# ThermoEagle.net
KiCad netlist of a schematic drawn in EAGLE
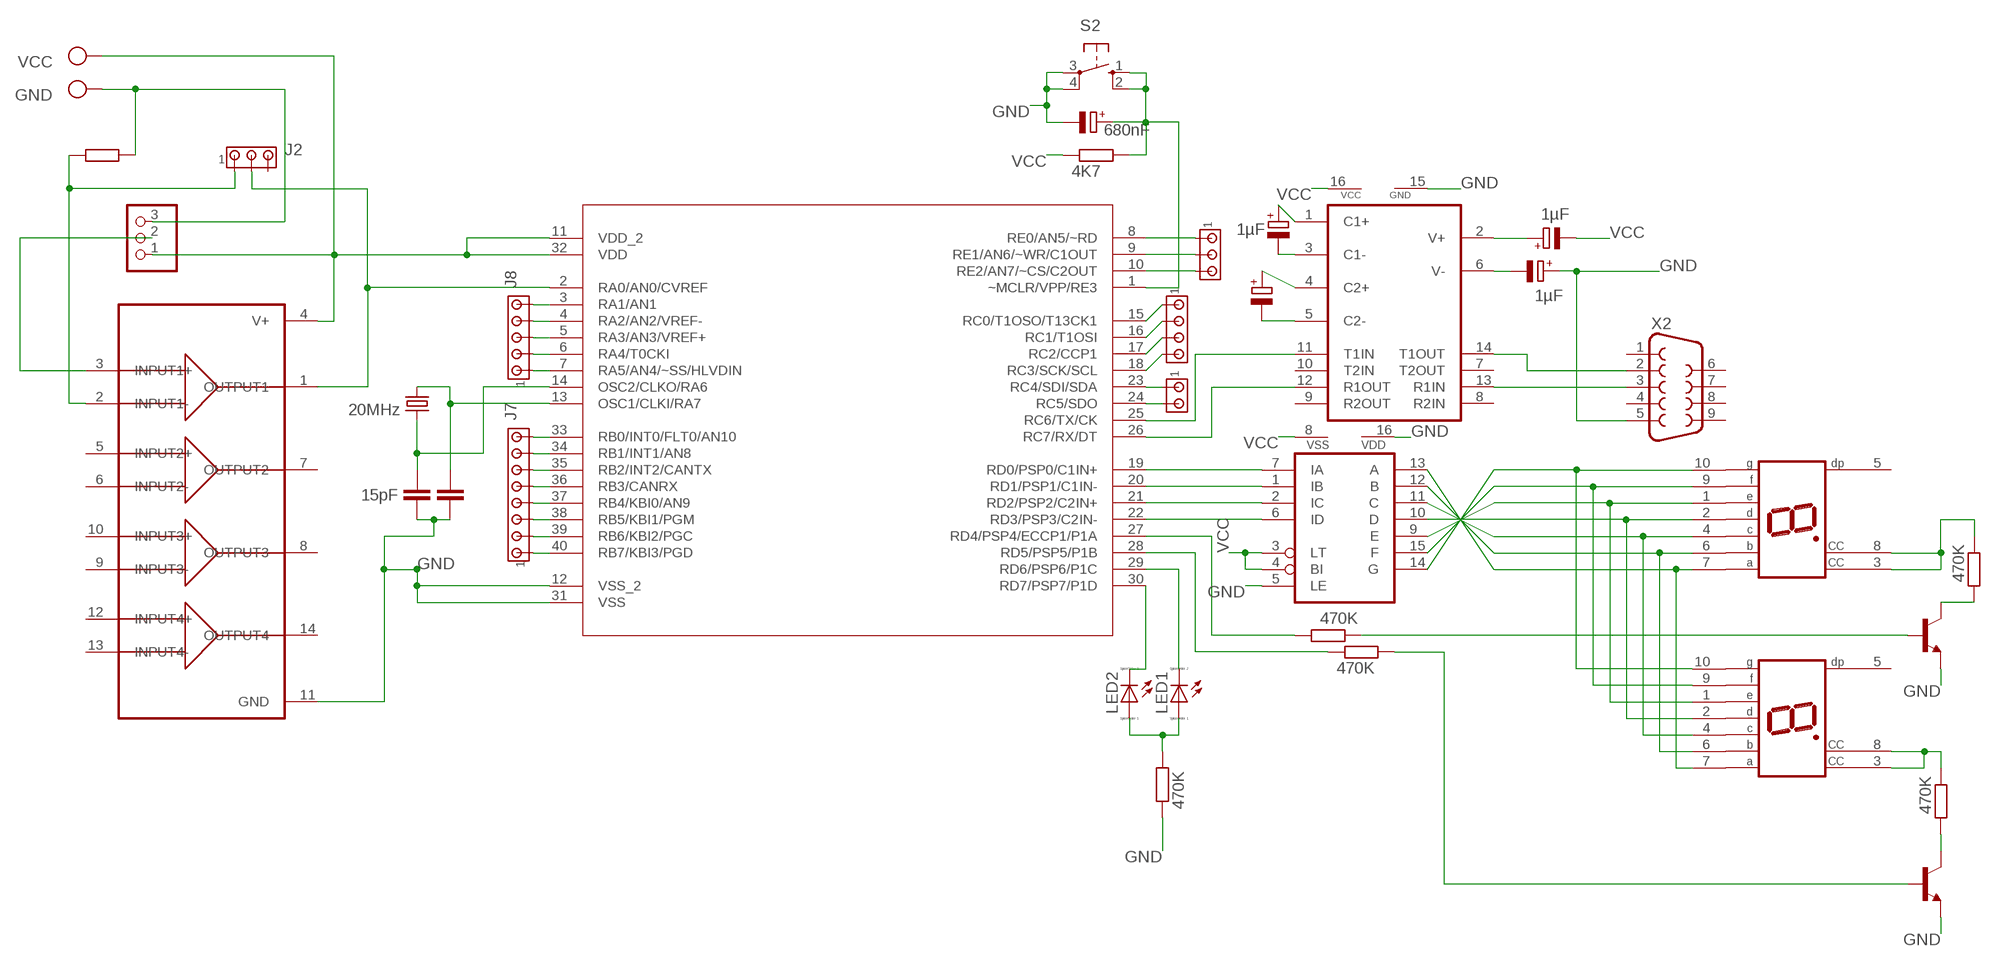
[diagram p0: schematic, sheet 1]

(export (version "E")
  (design (tool "Eeschema 10.0.6"))
  (components
    (comp (ref "C1")
      (value "1µF")
      (footprint "eagle-import:B45181B")
      (libsource (lib "eagle-import") (part "CPOL-EUB45181B"))
    )
    (comp (ref "C2")
      (value "1µF")
      (footprint "eagle-import:B45181B")
      (libsource (lib "eagle-import") (part "CPOL-EUB45181B"))
    )
    (comp (ref "C3")
      (value "1µF")
      (footprint "eagle-import:B45181B")
      (libsource (lib "eagle-import") (part "CPOL-EUB45181B"))
    )
    (comp (ref "C5")
      (value "1µF")
      (footprint "eagle-import:B45181B")
      (libsource (lib "eagle-import") (part "CPOL-EUB45181B"))
    )
    (comp (ref "C6")
      (value "15pF")
      (footprint "eagle-import:C050-025X075")
      (libsource (lib "eagle-import") (part "C-EU050-025X075"))
    )
    (comp (ref "C7")
      (value "C-EU050-025X075")
      (footprint "eagle-import:C050-025X075")
      (libsource (lib "eagle-import") (part "C-EU050-025X075"))
    )
    (comp (ref "C8")
      (value "680nF")
      (footprint "eagle-import:B45181C")
      (libsource (lib "eagle-import") (part "CPOL-EUB45181C"))
    )
    (comp (ref "DIS1")
      (value "HD-H103")
      (footprint "eagle-import:HDSP-M")
      (libsource (lib "eagle-import") (part "HD-H103"))
    )
    (comp (ref "DIS2")
      (value "HD-H103")
      (footprint "eagle-import:HDSP-M")
      (libsource (lib "eagle-import") (part "HD-H103"))
    )
    (comp (ref "IC1")
      (value "MAX232")
      (footprint "eagle-import:DIL16")
      (fields (field (name "MF") "MAXIM") (field (name "MPN") "MAX232ACPE+"))
      (libsource (lib "eagle-import") (part "MAX232"))
    )
    (comp (ref "IC2")
      (value "4511N")
      (footprint "eagle-import:DIL16")
      (libsource (lib "eagle-import") (part "4511N"))
    )
    (comp (ref "J1")
      (value "MTA04-100")
      (footprint "eagle-import:10X04MTA")
      (libsource (lib "eagle-import") (part "MTA04-100"))
    )
    (comp (ref "J2")
      (value "MTA03-100")
      (footprint "eagle-import:10X03MTA")
      (libsource (lib "eagle-import") (part "MTA03-100"))
    )
    (comp (ref "J3")
      (value "MTA02-100")
      (footprint "eagle-import:10X02MTA")
      (libsource (lib "eagle-import") (part "MTA02-100"))
    )
    (comp (ref "J4")
      (value "MTA03-100")
      (footprint "eagle-import:10X03MTA")
      (libsource (lib "eagle-import") (part "MTA03-100"))
    )
    (comp (ref "J7")
      (value "MTA08-100")
      (footprint "eagle-import:10X08MTA")
      (libsource (lib "eagle-import") (part "MTA08-100"))
    )
    (comp (ref "J8")
      (value "MTA05-100")
      (footprint "eagle-import:10X05MTA")
      (libsource (lib "eagle-import") (part "MTA05-100"))
    )
    (comp (ref "JP1")
      (value "PINHD-1X3")
      (footprint "eagle-import:1X03")
      (libsource (lib "eagle-import") (part "PINHD-1X3"))
    )
    (comp (ref "LED1")
      (value "LED_ELD260")
      (footprint "eagle-import:LED_LD260")
      (libsource (lib "eagle-import") (part "LED_ELD260"))
    )
    (comp (ref "LED2")
      (value "LED_ELD260")
      (footprint "eagle-import:LED_LD260")
      (libsource (lib "eagle-import") (part "LED_ELD260"))
    )
    (comp (ref "Q1")
      (value "20MHz")
      (footprint "eagle-import:HC18U-V")
      (libsource (lib "eagle-import") (part "CRYSTALHC18U-V"))
    )
    (comp (ref "R1")
      (value "470K")
      (footprint "eagle-import:0207_7")
      (libsource (lib "eagle-import") (part "R-EU_0207/7"))
    )
    (comp (ref "R2")
      (value "470K")
      (footprint "eagle-import:0207_7")
      (libsource (lib "eagle-import") (part "R-EU_0207/7"))
    )
    (comp (ref "R3")
      (value "470K")
      (footprint "eagle-import:0207_7")
      (libsource (lib "eagle-import") (part "R-EU_0207/7"))
    )
    (comp (ref "R10")
      (value "470K")
      (footprint "eagle-import:0207_7")
      (libsource (lib "eagle-import") (part "R-EU_0207/7"))
    )
    (comp (ref "R11")
      (value "470K")
      (footprint "eagle-import:0207_7")
      (libsource (lib "eagle-import") (part "R-EU_0207/7"))
    )
    (comp (ref "R13")
      (value "R-EU_0207/7")
      (footprint "eagle-import:0207_7")
      (libsource (lib "eagle-import") (part "R-EU_0207/7"))
    )
    (comp (ref "R14")
      (value "4K7")
      (footprint "eagle-import:0207_7")
      (libsource (lib "eagle-import") (part "R-EU_0207/7"))
    )
    (comp (ref "S2")
      (value "10-XX")
      (footprint "eagle-import:B3F-10XX")
      (fields (field (name "MPN") "B3F-1000"))
      (libsource (lib "eagle-import") (part "10-XX"))
    )
    (comp (ref "T1")
      (value "2N2219")
      (footprint "eagle-import:TO5")
      (libsource (lib "eagle-import") (part "2N2219"))
    )
    (comp (ref "T2")
      (value "2N2219")
      (footprint "eagle-import:TO5")
      (libsource (lib "eagle-import") (part "2N2219"))
    )
    (comp (ref "U$1")
      (value "PIC18F4585-I/P")
      (footprint "eagle-import:DIP254P1524X635-40")
      (fields (field (name "DIGI-KEY_PART_NUMBER") "PIC18F4585-I/P-ND") (field (name "MF") "Microchip"))
      (libsource (lib "eagle-import") (part "PIC18F4585-I/P"))
    )
    (comp (ref "U1")
      (value "LM324")
      (footprint "eagle-import:DIP790W51P254L1994H508Q14")
      (fields (field (name "MF") "STMicroelectronics"))
      (libsource (lib "eagle-import") (part "LM324"))
    )
    (comp (ref "X1")
      (value "AK300/2")
      (footprint "eagle-import:AK300_2")
      (libsource (lib "eagle-import") (part "AK300/2"))
    )
    (comp (ref "X2")
      (value "F09VB")
      (footprint "eagle-import:F09VB")
      (libsource (lib "eagle-import") (part "F09VB"))
    )
  )
  (nets
    (net (code "1") (name "/GND") (class "Default")
      (node (ref "C3") (pin "+") (pinfunction "+_+") (pintype "passive"))
      (node (ref "C6") (pin "2") (pinfunction "2_2") (pintype "passive"))
      (node (ref "C7") (pin "2") (pinfunction "2_2") (pintype "passive"))
      (node (ref "C8") (pin "-") (pinfunction "-_-") (pintype "passive"))
      (node (ref "IC1") (pin "15") (pinfunction "GND_15") (pintype "power_in"))
      (node (ref "IC2") (pin "16") (pinfunction "VDD_16") (pintype "power_in"))
      (node (ref "IC2") (pin "5") (pinfunction "LE_5") (pintype "input"))
      (node (ref "JP1") (pin "3") (pinfunction "3_3") (pintype "passive"))
      (node (ref "R1") (pin "1") (pinfunction "1_1") (pintype "passive"))
      (node (ref "R13") (pin "1") (pinfunction "1_1") (pintype "passive"))
      (node (ref "S2") (pin "3") (pinfunction "P_3") (pintype "passive"))
      (node (ref "S2") (pin "4") (pinfunction "P1_4") (pintype "passive"))
      (node (ref "T1") (pin "1") (pinfunction "E_1") (pintype "passive"))
      (node (ref "T2") (pin "1") (pinfunction "E_1") (pintype "passive"))
      (node (ref "U$1") (pin "12") (pinfunction "VSS_2_12") (pintype "power_in"))
      (node (ref "U$1") (pin "31") (pinfunction "VSS_31") (pintype "power_in"))
      (node (ref "U1") (pin "11") (pinfunction "GND_11") (pintype "power_in"))
      (node (ref "X1") (pin "2") (pinfunction "KL_2") (pintype "passive"))
      (node (ref "X2") (pin "5") (pinfunction "5_5") (pintype "passive"))
    )
    (net (code "2") (name "/VCC") (class "Default")
      (node (ref "C2") (pin "-") (pinfunction "-_-") (pintype "passive"))
      (node (ref "IC1") (pin "16") (pinfunction "VCC_16") (pintype "power_in"))
      (node (ref "IC2") (pin "3") (pinfunction "LT_3") (pintype "input"))
      (node (ref "IC2") (pin "4") (pinfunction "BI_4") (pintype "input"))
      (node (ref "IC2") (pin "8") (pinfunction "VSS_8") (pintype "power_in"))
      (node (ref "JP1") (pin "1") (pinfunction "1_1") (pintype "passive"))
      (node (ref "R14") (pin "1") (pinfunction "1_1") (pintype "passive"))
      (node (ref "U$1") (pin "11") (pinfunction "VDD_2_11") (pintype "power_in"))
      (node (ref "U$1") (pin "32") (pinfunction "VDD_32") (pintype "power_in"))
      (node (ref "U1") (pin "4") (pinfunction "V+_4") (pintype "power_in"))
      (node (ref "X1") (pin "1") (pinfunction "KL_1") (pintype "passive"))
    )
    (net (code "3") (name "Net-(DIS1-A)") (class "Default")
      (node (ref "DIS1") (pin "7") (pinfunction "A_7") (pintype "passive"))
      (node (ref "DIS2") (pin "7") (pinfunction "A_7") (pintype "passive"))
      (node (ref "IC2") (pin "13") (pinfunction "A_13") (pintype "output"))
    )
    (net (code "4") (name "Net-(DIS1-B)") (class "Default")
      (node (ref "DIS1") (pin "6") (pinfunction "B_6") (pintype "passive"))
      (node (ref "DIS2") (pin "6") (pinfunction "B_6") (pintype "passive"))
      (node (ref "IC2") (pin "12") (pinfunction "B_12") (pintype "output"))
    )
    (net (code "5") (name "Net-(DIS1-C)") (class "Default")
      (node (ref "DIS1") (pin "4") (pinfunction "C_4") (pintype "passive"))
      (node (ref "DIS2") (pin "4") (pinfunction "C_4") (pintype "passive"))
      (node (ref "IC2") (pin "11") (pinfunction "C_11") (pintype "output"))
    )
    (net (code "6") (name "Net-(DIS1-CC-Pad3)") (class "Default")
      (node (ref "DIS1") (pin "3") (pinfunction "CC_3") (pintype "passive"))
      (node (ref "DIS1") (pin "8") (pinfunction "CC_8") (pintype "passive"))
      (node (ref "R3") (pin "1") (pinfunction "1_1") (pintype "passive"))
    )
    (net (code "7") (name "Net-(DIS1-D)") (class "Default")
      (node (ref "DIS1") (pin "2") (pinfunction "D_2") (pintype "passive"))
      (node (ref "DIS2") (pin "2") (pinfunction "D_2") (pintype "passive"))
      (node (ref "IC2") (pin "10") (pinfunction "D_10") (pintype "output"))
    )
    (net (code "8") (name "Net-(DIS1-E)") (class "Default")
      (node (ref "DIS1") (pin "1") (pinfunction "E_1") (pintype "passive"))
      (node (ref "DIS2") (pin "1") (pinfunction "E_1") (pintype "passive"))
      (node (ref "IC2") (pin "9") (pinfunction "E_9") (pintype "output"))
    )
    (net (code "9") (name "Net-(DIS1-F)") (class "Default")
      (node (ref "DIS1") (pin "9") (pinfunction "F_9") (pintype "passive"))
      (node (ref "DIS2") (pin "9") (pinfunction "F_9") (pintype "passive"))
      (node (ref "IC2") (pin "15") (pinfunction "F_15") (pintype "output"))
    )
    (net (code "10") (name "Net-(DIS1-G)") (class "Default")
      (node (ref "DIS1") (pin "10") (pinfunction "G_10") (pintype "passive"))
      (node (ref "DIS2") (pin "10") (pinfunction "G_10") (pintype "passive"))
      (node (ref "IC2") (pin "14") (pinfunction "G_14") (pintype "output"))
    )
    (net (code "11") (name "Net-(DIS2-CC-Pad3)") (class "Default")
      (node (ref "DIS2") (pin "3") (pinfunction "CC_3") (pintype "passive"))
      (node (ref "DIS2") (pin "8") (pinfunction "CC_8") (pintype "passive"))
      (node (ref "R2") (pin "1") (pinfunction "1_1") (pintype "passive"))
    )
    (net (code "12") (name "Net-(IC1A-C1+)") (class "Default")
      (node (ref "C1") (pin "+") (pinfunction "+_+") (pintype "passive"))
      (node (ref "IC1") (pin "1") (pinfunction "C1+_1") (pintype "bidirectional"))
    )
    (net (code "13") (name "Net-(IC1A-C1-)") (class "Default")
      (node (ref "C1") (pin "-") (pinfunction "-_-") (pintype "passive"))
      (node (ref "IC1") (pin "3") (pinfunction "C1-_3") (pintype "bidirectional"))
    )
    (net (code "14") (name "Net-(IC1A-C2+)") (class "Default")
      (node (ref "C5") (pin "+") (pinfunction "+_+") (pintype "passive"))
      (node (ref "IC1") (pin "4") (pinfunction "C2+_4") (pintype "bidirectional"))
    )
    (net (code "15") (name "Net-(IC1A-C2-)") (class "Default")
      (node (ref "C5") (pin "-") (pinfunction "-_-") (pintype "passive"))
      (node (ref "IC1") (pin "5") (pinfunction "C2-_5") (pintype "bidirectional"))
    )
    (net (code "16") (name "Net-(IC1A-R1IN)") (class "Default")
      (node (ref "IC1") (pin "13") (pinfunction "R1IN_13") (pintype "input"))
      (node (ref "X2") (pin "3") (pinfunction "3_3") (pintype "passive"))
    )
    (net (code "17") (name "Net-(IC1A-R1OUT)") (class "Default")
      (node (ref "IC1") (pin "12") (pinfunction "R1OUT_12") (pintype "output"))
      (node (ref "U$1") (pin "26") (pinfunction "RC7/RX/DT_26") (pintype "bidirectional"))
    )
    (net (code "18") (name "Net-(IC1A-T1IN)") (class "Default")
      (node (ref "IC1") (pin "11") (pinfunction "T1IN_11") (pintype "input"))
      (node (ref "U$1") (pin "25") (pinfunction "RC6/TX/CK_25") (pintype "bidirectional"))
    )
    (net (code "19") (name "Net-(IC1A-T1OUT)") (class "Default")
      (node (ref "IC1") (pin "14") (pinfunction "T1OUT_14") (pintype "output"))
      (node (ref "X2") (pin "2") (pinfunction "2_2") (pintype "passive"))
    )
    (net (code "20") (name "Net-(IC1A-V+)") (class "Default")
      (node (ref "C2") (pin "+") (pinfunction "+_+") (pintype "passive"))
      (node (ref "IC1") (pin "2") (pinfunction "V+_2") (pintype "bidirectional"))
    )
    (net (code "21") (name "Net-(IC1A-V-)") (class "Default")
      (node (ref "C3") (pin "-") (pinfunction "-_-") (pintype "passive"))
      (node (ref "IC1") (pin "6") (pinfunction "V-_6") (pintype "bidirectional"))
    )
    (net (code "22") (name "Net-(IC2A-IA)") (class "Default")
      (node (ref "IC2") (pin "7") (pinfunction "IA_7") (pintype "input"))
      (node (ref "U$1") (pin "19") (pinfunction "RD0/PSP0/C1IN+_19") (pintype "bidirectional"))
    )
    (net (code "23") (name "Net-(IC2A-IB)") (class "Default")
      (node (ref "IC2") (pin "1") (pinfunction "IB_1") (pintype "input"))
      (node (ref "U$1") (pin "20") (pinfunction "RD1/PSP1/C1IN-_20") (pintype "bidirectional"))
    )
    (net (code "24") (name "Net-(IC2A-IC)") (class "Default")
      (node (ref "IC2") (pin "2") (pinfunction "IC_2") (pintype "input"))
      (node (ref "U$1") (pin "21") (pinfunction "RD2/PSP2/C2IN+_21") (pintype "bidirectional"))
    )
    (net (code "25") (name "Net-(IC2A-ID)") (class "Default")
      (node (ref "IC2") (pin "6") (pinfunction "ID_6") (pintype "input"))
      (node (ref "U$1") (pin "22") (pinfunction "RD3/PSP3/C2IN-_22") (pintype "bidirectional"))
    )
    (net (code "26") (name "Net-(LED1-C)") (class "Default")
      (node (ref "LED1") (pin "K") (pinfunction "C_K") (pintype "passive"))
      (node (ref "U$1") (pin "29") (pinfunction "RD6/PSP6/P1C_29") (pintype "bidirectional"))
    )
    (net (code "27") (name "Net-(LED1-PadA)") (class "Default")
      (node (ref "LED1") (pin "A") (pinfunction "A_A") (pintype "passive"))
      (node (ref "LED2") (pin "A") (pinfunction "A_A") (pintype "passive"))
      (node (ref "R1") (pin "2") (pinfunction "2_2") (pintype "passive"))
    )
    (net (code "28") (name "Net-(LED2-C)") (class "Default")
      (node (ref "LED2") (pin "K") (pinfunction "C_K") (pintype "passive"))
      (node (ref "U$1") (pin "30") (pinfunction "RD7/PSP7/P1D_30") (pintype "bidirectional"))
    )
    (net (code "29") (name "Net-(S2-S)") (class "Default")
      (node (ref "C8") (pin "+") (pinfunction "+_+") (pintype "passive"))
      (node (ref "R14") (pin "2") (pinfunction "2_2") (pintype "passive"))
      (node (ref "S2") (pin "1") (pinfunction "S_1") (pintype "passive"))
      (node (ref "S2") (pin "2") (pinfunction "S1_2") (pintype "passive"))
      (node (ref "U$1") (pin "1") (pinfunction "~{MCLR/VPP/RE3}_1") (pintype "bidirectional"))
    )
    (net (code "30") (name "Net-(T1-B)") (class "Default")
      (node (ref "R11") (pin "2") (pinfunction "2_2") (pintype "passive"))
      (node (ref "T1") (pin "2") (pinfunction "B_2") (pintype "passive"))
    )
    (net (code "31") (name "Net-(T1-C)") (class "Default")
      (node (ref "R2") (pin "2") (pinfunction "2_2") (pintype "passive"))
      (node (ref "T1") (pin "3") (pinfunction "C_3") (pintype "passive"))
    )
    (net (code "32") (name "Net-(T2-B)") (class "Default")
      (node (ref "R10") (pin "2") (pinfunction "2_2") (pintype "passive"))
      (node (ref "T2") (pin "2") (pinfunction "B_2") (pintype "passive"))
    )
    (net (code "33") (name "Net-(T2-C)") (class "Default")
      (node (ref "R3") (pin "2") (pinfunction "2_2") (pintype "passive"))
      (node (ref "T2") (pin "3") (pinfunction "C_3") (pintype "passive"))
    )
    (net (code "34") (name "Net-(U$1-OSC1{slash}CLKI{slash}RA7)") (class "Default")
      (node (ref "C7") (pin "1") (pinfunction "1_1") (pintype "passive"))
      (node (ref "Q1") (pin "2") (pinfunction "2_2") (pintype "passive"))
      (node (ref "U$1") (pin "13") (pinfunction "OSC1/CLKI/RA7_13") (pintype "bidirectional"))
    )
    (net (code "35") (name "Net-(U$1-OSC2{slash}CLKO{slash}RA6)") (class "Default")
      (node (ref "C6") (pin "1") (pinfunction "1_1") (pintype "passive"))
      (node (ref "Q1") (pin "1") (pinfunction "1_1") (pintype "passive"))
      (node (ref "U$1") (pin "14") (pinfunction "OSC2/CLKO/RA6_14") (pintype "bidirectional"))
    )
    (net (code "36") (name "Net-(U$1-RA0{slash}AN0{slash}CVREF)") (class "Default")
      (node (ref "J2") (pin "2") (pinfunction "2_2") (pintype "passive"))
      (node (ref "U$1") (pin "2") (pinfunction "RA0/AN0/CVREF_2") (pintype "bidirectional"))
      (node (ref "U1") (pin "1") (pinfunction "OUTPUT1_1") (pintype "output"))
    )
    (net (code "37") (name "Net-(U$1-RA1{slash}AN1)") (class "Default")
      (node (ref "J8") (pin "5") (pinfunction "5_5") (pintype "passive"))
      (node (ref "U$1") (pin "3") (pinfunction "RA1/AN1_3") (pintype "bidirectional"))
    )
    (net (code "38") (name "Net-(U$1-RA2{slash}AN2{slash}VREF-)") (class "Default")
      (node (ref "J8") (pin "4") (pinfunction "4_4") (pintype "passive"))
      (node (ref "U$1") (pin "4") (pinfunction "RA2/AN2/VREF-_4") (pintype "bidirectional"))
    )
    (net (code "39") (name "Net-(U$1-RA3{slash}AN3{slash}VREF+)") (class "Default")
      (node (ref "J8") (pin "3") (pinfunction "3_3") (pintype "passive"))
      (node (ref "U$1") (pin "5") (pinfunction "RA3/AN3/VREF+_5") (pintype "bidirectional"))
    )
    (net (code "40") (name "Net-(U$1-RA4{slash}T0CKI)") (class "Default")
      (node (ref "J8") (pin "2") (pinfunction "2_2") (pintype "passive"))
      (node (ref "U$1") (pin "6") (pinfunction "RA4/T0CKI_6") (pintype "bidirectional"))
    )
    (net (code "41") (name "Net-(U$1-RA5{slash}AN4{slash}~{SS{slash}HLVDIN})") (class "Default")
      (node (ref "J8") (pin "1") (pinfunction "1_1") (pintype "passive"))
      (node (ref "U$1") (pin "7") (pinfunction "RA5/AN4/~{SS/HLVDIN}_7") (pintype "bidirectional"))
    )
    (net (code "42") (name "Net-(U$1-RB0{slash}INT0{slash}FLT0{slash}AN10)") (class "Default")
      (node (ref "J7") (pin "8") (pinfunction "8_8") (pintype "passive"))
      (node (ref "U$1") (pin "33") (pinfunction "RB0/INT0/FLT0/AN10_33") (pintype "bidirectional"))
    )
    (net (code "43") (name "Net-(U$1-RB1{slash}INT1{slash}AN8)") (class "Default")
      (node (ref "J7") (pin "7") (pinfunction "7_7") (pintype "passive"))
      (node (ref "U$1") (pin "34") (pinfunction "RB1/INT1/AN8_34") (pintype "bidirectional"))
    )
    (net (code "44") (name "Net-(U$1-RB2{slash}INT2{slash}CANTX)") (class "Default")
      (node (ref "J7") (pin "6") (pinfunction "6_6") (pintype "passive"))
      (node (ref "U$1") (pin "35") (pinfunction "RB2/INT2/CANTX_35") (pintype "bidirectional"))
    )
    (net (code "45") (name "Net-(U$1-RB3{slash}CANRX)") (class "Default")
      (node (ref "J7") (pin "5") (pinfunction "5_5") (pintype "passive"))
      (node (ref "U$1") (pin "36") (pinfunction "RB3/CANRX_36") (pintype "bidirectional"))
    )
    (net (code "46") (name "Net-(U$1-RB4{slash}KBI0{slash}AN9)") (class "Default")
      (node (ref "J7") (pin "4") (pinfunction "4_4") (pintype "passive"))
      (node (ref "U$1") (pin "37") (pinfunction "RB4/KBI0/AN9_37") (pintype "bidirectional"))
    )
    (net (code "47") (name "Net-(U$1-RB5{slash}KBI1{slash}PGM)") (class "Default")
      (node (ref "J7") (pin "3") (pinfunction "3_3") (pintype "passive"))
      (node (ref "U$1") (pin "38") (pinfunction "RB5/KBI1/PGM_38") (pintype "bidirectional"))
    )
    (net (code "48") (name "Net-(U$1-RB6{slash}KBI2{slash}PGC)") (class "Default")
      (node (ref "J7") (pin "2") (pinfunction "2_2") (pintype "passive"))
      (node (ref "U$1") (pin "39") (pinfunction "RB6/KBI2/PGC_39") (pintype "bidirectional"))
    )
    (net (code "49") (name "Net-(U$1-RB7{slash}KBI3{slash}PGD)") (class "Default")
      (node (ref "J7") (pin "1") (pinfunction "1_1") (pintype "passive"))
      (node (ref "U$1") (pin "40") (pinfunction "RB7/KBI3/PGD_40") (pintype "bidirectional"))
    )
    (net (code "50") (name "Net-(U$1-RC0{slash}T1OSO{slash}T13CK1)") (class "Default")
      (node (ref "J1") (pin "1") (pinfunction "1_1") (pintype "passive"))
      (node (ref "U$1") (pin "15") (pinfunction "RC0/T1OSO/T13CK1_15") (pintype "bidirectional"))
    )
    (net (code "51") (name "Net-(U$1-RC1{slash}T1OSI)") (class "Default")
      (node (ref "J1") (pin "2") (pinfunction "2_2") (pintype "passive"))
      (node (ref "U$1") (pin "16") (pinfunction "RC1/T1OSI_16") (pintype "bidirectional"))
    )
    (net (code "52") (name "Net-(U$1-RC2{slash}CCP1)") (class "Default")
      (node (ref "J1") (pin "3") (pinfunction "3_3") (pintype "passive"))
      (node (ref "U$1") (pin "17") (pinfunction "RC2/CCP1_17") (pintype "bidirectional"))
    )
    (net (code "53") (name "Net-(U$1-RC3{slash}SCK{slash}SCL)") (class "Default")
      (node (ref "J1") (pin "4") (pinfunction "4_4") (pintype "passive"))
      (node (ref "U$1") (pin "18") (pinfunction "RC3/SCK/SCL_18") (pintype "bidirectional"))
    )
    (net (code "54") (name "Net-(U$1-RC4{slash}SDI{slash}SDA)") (class "Default")
      (node (ref "J3") (pin "1") (pinfunction "1_1") (pintype "passive"))
      (node (ref "U$1") (pin "23") (pinfunction "RC4/SDI/SDA_23") (pintype "bidirectional"))
    )
    (net (code "55") (name "Net-(U$1-RC5{slash}SDO)") (class "Default")
      (node (ref "J3") (pin "2") (pinfunction "2_2") (pintype "passive"))
      (node (ref "U$1") (pin "24") (pinfunction "RC5/SDO_24") (pintype "bidirectional"))
    )
    (net (code "56") (name "Net-(U$1-RD4{slash}PSP4{slash}ECCP1{slash}P1A)") (class "Default")
      (node (ref "R10") (pin "1") (pinfunction "1_1") (pintype "passive"))
      (node (ref "U$1") (pin "27") (pinfunction "RD4/PSP4/ECCP1/P1A_27") (pintype "bidirectional"))
    )
    (net (code "57") (name "Net-(U$1-RD5{slash}PSP5{slash}P1B)") (class "Default")
      (node (ref "R11") (pin "1") (pinfunction "1_1") (pintype "passive"))
      (node (ref "U$1") (pin "28") (pinfunction "RD5/PSP5/P1B_28") (pintype "bidirectional"))
    )
    (net (code "58") (name "Net-(U$1-RE0{slash}AN5{slash}~{RD})") (class "Default")
      (node (ref "J4") (pin "1") (pinfunction "1_1") (pintype "passive"))
      (node (ref "U$1") (pin "8") (pinfunction "RE0/AN5/~{RD}_8") (pintype "bidirectional"))
    )
    (net (code "59") (name "Net-(U$1-RE1{slash}AN6{slash}~{WR{slash}C1OUT})") (class "Default")
      (node (ref "J4") (pin "2") (pinfunction "2_2") (pintype "passive"))
      (node (ref "U$1") (pin "9") (pinfunction "RE1/AN6/~{WR/C1OUT}_9") (pintype "bidirectional"))
    )
    (net (code "60") (name "Net-(U$1-RE2{slash}AN7{slash}~{CS{slash}C2OUT})") (class "Default")
      (node (ref "J4") (pin "3") (pinfunction "3_3") (pintype "passive"))
      (node (ref "U$1") (pin "10") (pinfunction "RE2/AN7/~{CS/C2OUT}_10") (pintype "bidirectional"))
    )
    (net (code "61") (name "Net-(U1-INPUT1+)") (class "Default")
      (node (ref "JP1") (pin "2") (pinfunction "2_2") (pintype "passive"))
      (node (ref "U1") (pin "3") (pinfunction "INPUT1+_3") (pintype "input"))
    )
    (net (code "62") (name "Net-(U1-INPUT1-)") (class "Default")
      (node (ref "J2") (pin "1") (pinfunction "1_1") (pintype "passive"))
      (node (ref "R13") (pin "2") (pinfunction "2_2") (pintype "passive"))
      (node (ref "U1") (pin "2") (pinfunction "INPUT1-_2") (pintype "input"))
    )
    (net (code "63") (name "unconnected-(DIS1-DP-Pad5)") (class "Default")
      (node (ref "DIS1") (pin "5") (pinfunction "DP_5") (pintype "passive"))
    )
    (net (code "64") (name "unconnected-(DIS2-DP-Pad5)") (class "Default")
      (node (ref "DIS2") (pin "5") (pinfunction "DP_5") (pintype "passive"))
    )
    (net (code "65") (name "unconnected-(IC1A-R2IN-Pad8)") (class "Default")
      (node (ref "IC1") (pin "8") (pinfunction "R2IN_8") (pintype "input"))
    )
    (net (code "66") (name "unconnected-(IC1A-R2OUT-Pad9)") (class "Default")
      (node (ref "IC1") (pin "9") (pinfunction "R2OUT_9") (pintype "output"))
    )
    (net (code "67") (name "unconnected-(IC1A-T2IN-Pad10)") (class "Default")
      (node (ref "IC1") (pin "10") (pinfunction "T2IN_10") (pintype "input"))
    )
    (net (code "68") (name "unconnected-(IC1A-T2OUT-Pad7)") (class "Default")
      (node (ref "IC1") (pin "7") (pinfunction "T2OUT_7") (pintype "output"))
    )
    (net (code "69") (name "unconnected-(J2-Pad3)") (class "Default")
      (node (ref "J2") (pin "3") (pinfunction "3_3") (pintype "passive"))
    )
    (net (code "70") (name "unconnected-(U1-INPUT2+-Pad5)") (class "Default")
      (node (ref "U1") (pin "5") (pinfunction "INPUT2+_5") (pintype "input"))
    )
    (net (code "71") (name "unconnected-(U1-INPUT2--Pad6)") (class "Default")
      (node (ref "U1") (pin "6") (pinfunction "INPUT2-_6") (pintype "input"))
    )
    (net (code "72") (name "unconnected-(U1-INPUT3+-Pad10)") (class "Default")
      (node (ref "U1") (pin "10") (pinfunction "INPUT3+_10") (pintype "input"))
    )
    (net (code "73") (name "unconnected-(U1-INPUT3--Pad9)") (class "Default")
      (node (ref "U1") (pin "9") (pinfunction "INPUT3-_9") (pintype "input"))
    )
    (net (code "74") (name "unconnected-(U1-INPUT4+-Pad12)") (class "Default")
      (node (ref "U1") (pin "12") (pinfunction "INPUT4+_12") (pintype "input"))
    )
    (net (code "75") (name "unconnected-(U1-INPUT4--Pad13)") (class "Default")
      (node (ref "U1") (pin "13") (pinfunction "INPUT4-_13") (pintype "input"))
    )
    (net (code "76") (name "unconnected-(U1-OUTPUT2-Pad7)") (class "Default")
      (node (ref "U1") (pin "7") (pinfunction "OUTPUT2_7") (pintype "output"))
    )
    (net (code "77") (name "unconnected-(U1-OUTPUT3-Pad8)") (class "Default")
      (node (ref "U1") (pin "8") (pinfunction "OUTPUT3_8") (pintype "output"))
    )
    (net (code "78") (name "unconnected-(U1-OUTPUT4-Pad14)") (class "Default")
      (node (ref "U1") (pin "14") (pinfunction "OUTPUT4_14") (pintype "output"))
    )
    (net (code "79") (name "unconnected-(X2-Pad1)") (class "Default")
      (node (ref "X2") (pin "1") (pinfunction "1_1") (pintype "passive"))
    )
    (net (code "80") (name "unconnected-(X2-Pad4)") (class "Default")
      (node (ref "X2") (pin "4") (pinfunction "4_4") (pintype "passive"))
    )
    (net (code "81") (name "unconnected-(X2-Pad6)") (class "Default")
      (node (ref "X2") (pin "6") (pinfunction "6_6") (pintype "passive"))
    )
    (net (code "82") (name "unconnected-(X2-Pad7)") (class "Default")
      (node (ref "X2") (pin "7") (pinfunction "7_7") (pintype "passive"))
    )
    (net (code "83") (name "unconnected-(X2-Pad8)") (class "Default")
      (node (ref "X2") (pin "8") (pinfunction "8_8") (pintype "passive"))
    )
    (net (code "84") (name "unconnected-(X2-Pad9)") (class "Default")
      (node (ref "X2") (pin "9") (pinfunction "9_9") (pintype "passive"))
    )
  )
)
